# 18_RK3588_PCIE30_PCIE20_SATA30.net
KiCad netlist of a schematic drawn in Altium Designer
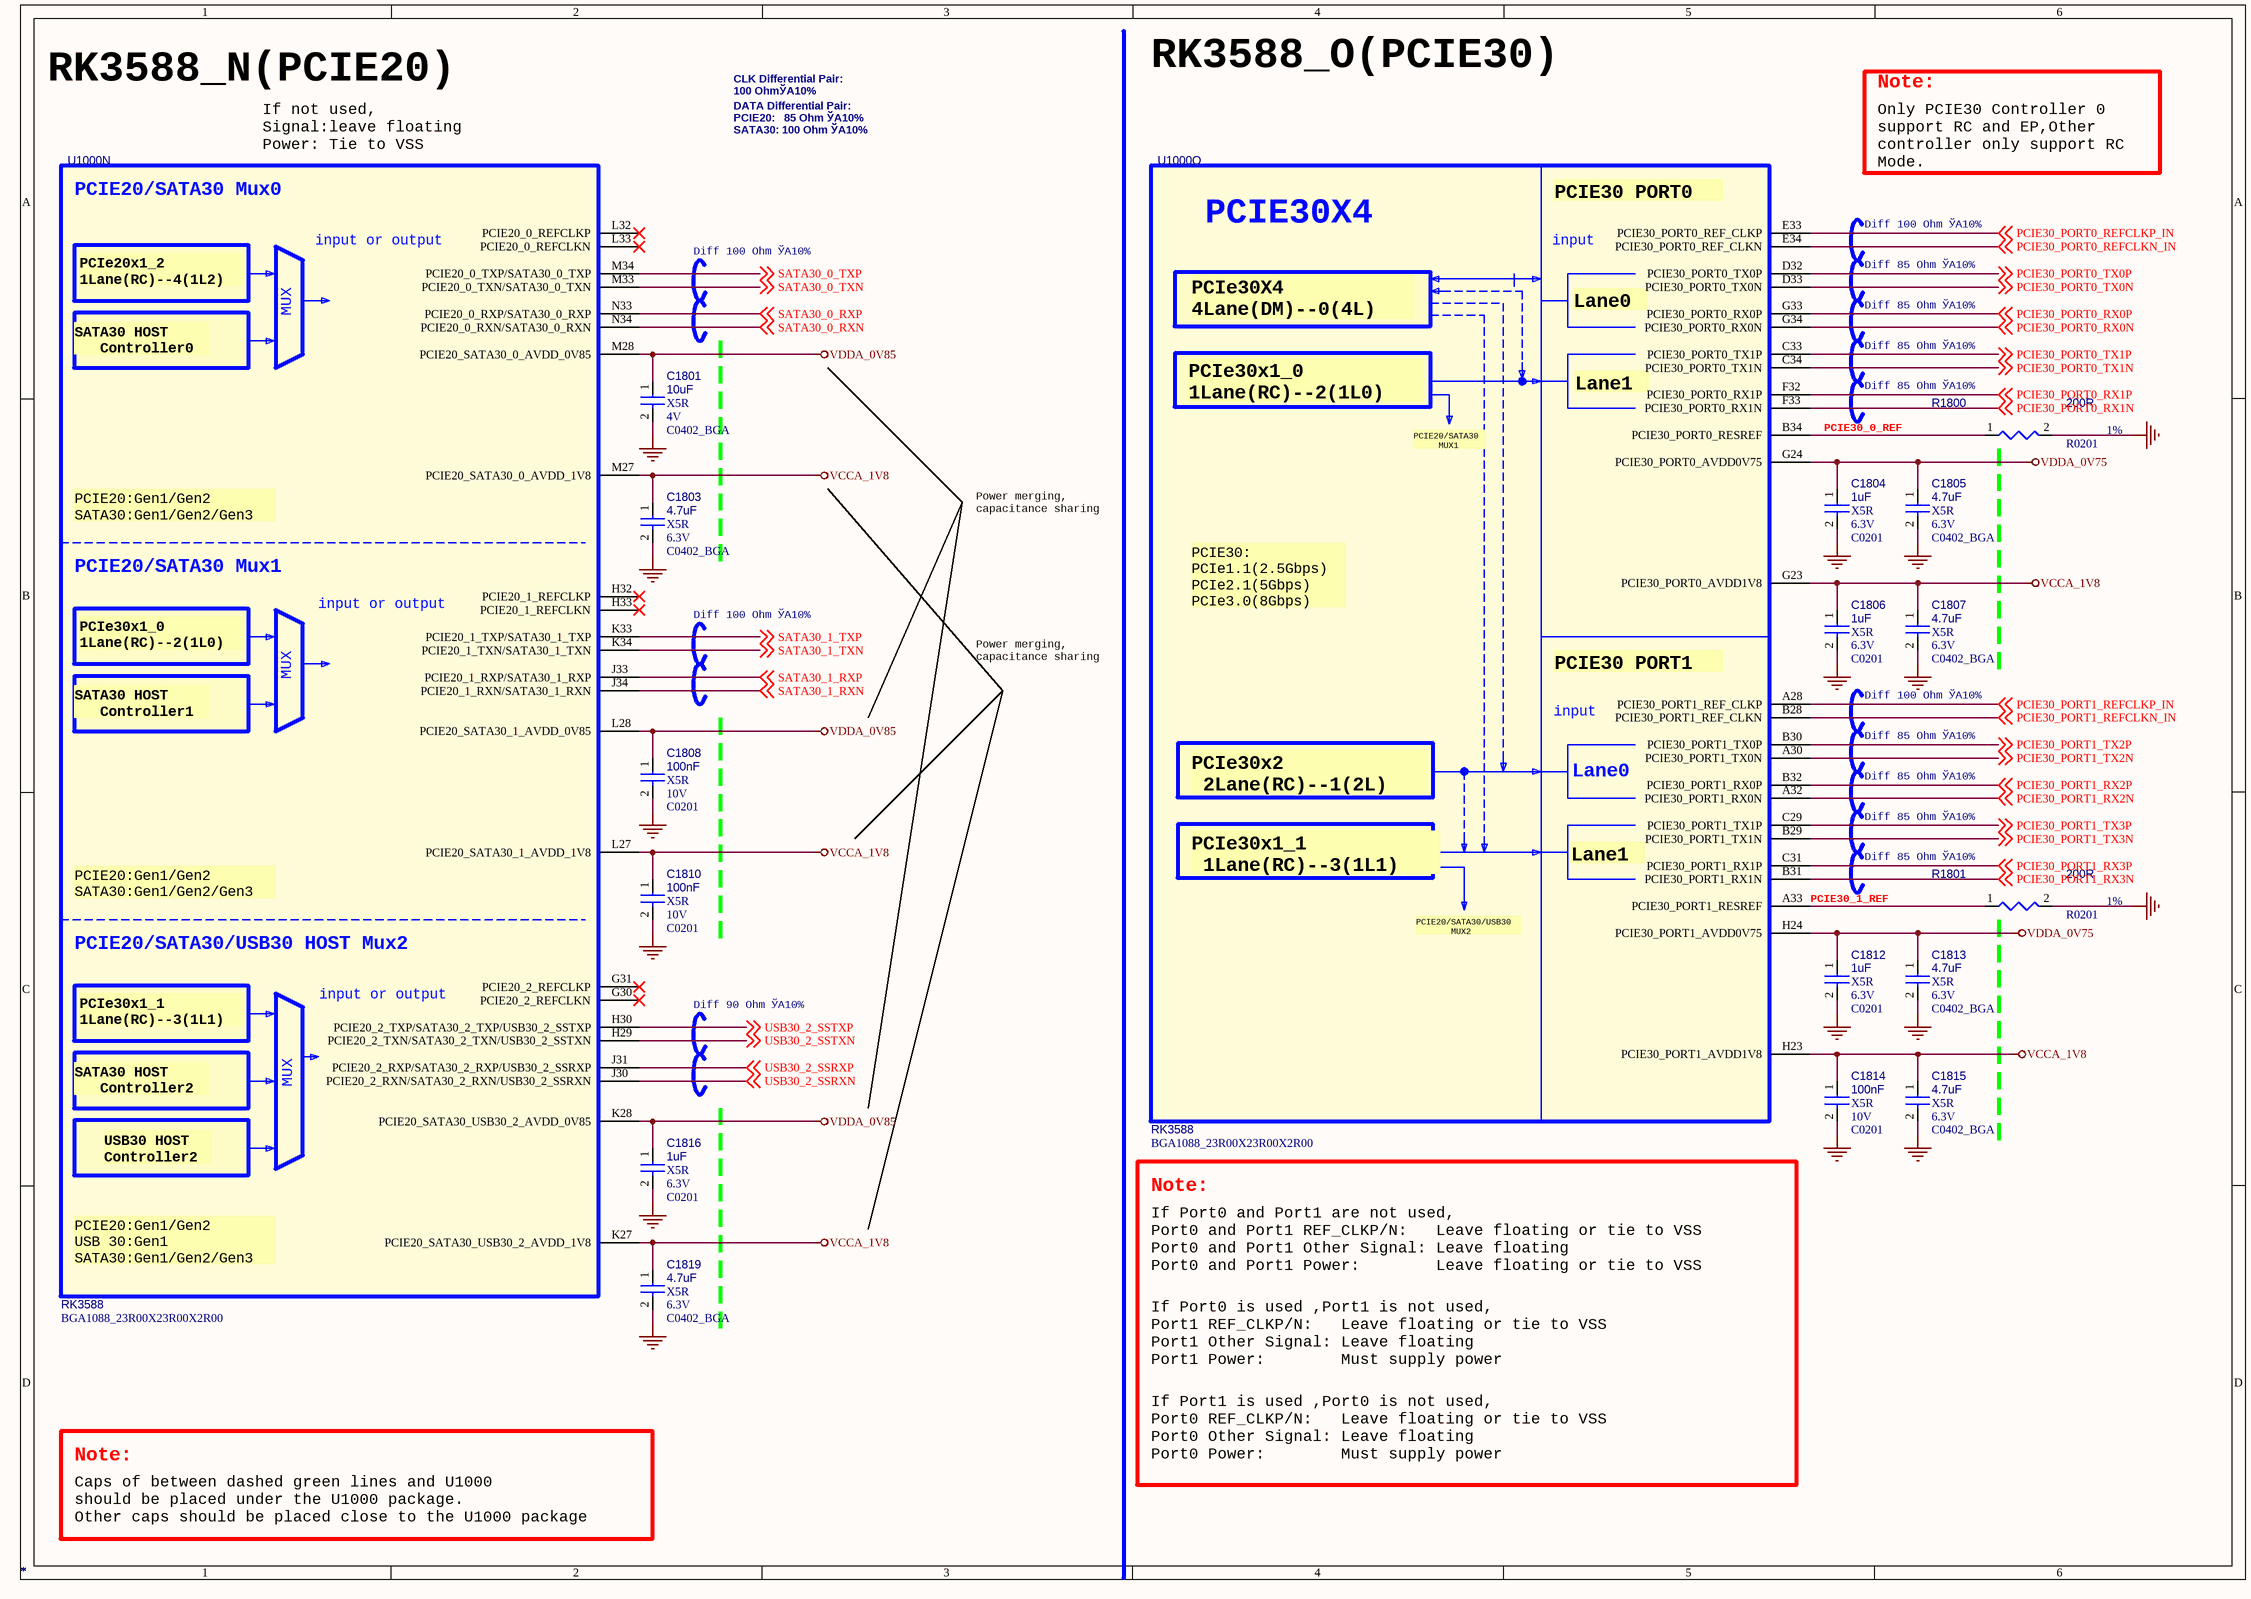
[diagram p0: 18.RK3588_PCIE30_PCIE20_SATA30.SchDoc]

(export (version "E")
  (design (tool "Eeschema 10.0.6"))
  (components
    (comp (ref "C1801")
      (value "*")
      (footprint "C0402_BGA")
      (description "cap,10.00uF,+/-20%,4V,X5R,C0402")
      (fields
        (field (name "VOLTAGE") "4V")
        (field (name "PCB FOOTPRINT") "C0402_BGA")
        (field (name "DIELECTRIC") "X5R")
        (field (name "MANUFACTURER") "YAGEO")
        (field (name "TOLERANCE") "20%")
        (field (name "ALTIUM_UNNAMED_1") "10uF")
        (field (name "CREATED BY") "JJJ")
      )
      (libsource (lib "*") (part "CAP NP"))
    )
    (comp (ref "C1803")
      (value "*")
      (footprint "C0402_BGA")
      (description "cap,4.70uF,+/-10%,6.3V,X5R,C0402")
      (fields
        (field (name "VOLTAGE") "6.3V")
        (field (name "PCB FOOTPRINT") "C0402_BGA")
        (field (name "DIELECTRIC") "X5R")
        (field (name "MANUFACTURER") "TDK")
        (field (name "TOLERANCE") "10%")
        (field (name "ALTIUM_UNNAMED_1") "4.7uF")
        (field (name "CREATED BY") "JJJ")
      )
      (libsource (lib "*") (part "CAP NP"))
    )
    (comp (ref "C1804")
      (value "*")
      (footprint "C0201")
      (description "cap,1.00uF,+/-20%,6.3V,X5R,C0201")
      (fields
        (field (name "VOLTAGE") "6.3V")
        (field (name "PCB FOOTPRINT") "C0201")
        (field (name "DIELECTRIC") "X5R")
        (field (name "TOLERANCE") "20%")
        (field (name "MANUFACTURER") "TDK")
        (field (name "ALTIUM_UNNAMED_1") "1uF")
        (field (name "CREATED BY") "JJJ")
      )
      (libsource (lib "*") (part "CAP NP"))
    )
    (comp (ref "C1805")
      (value "*")
      (footprint "C0402_BGA")
      (description "cap,4.70uF,+/-10%,6.3V,X5R,C0402")
      (fields
        (field (name "VOLTAGE") "6.3V")
        (field (name "PCB FOOTPRINT") "C0402_BGA")
        (field (name "DIELECTRIC") "X5R")
        (field (name "MANUFACTURER") "TDK")
        (field (name "TOLERANCE") "10%")
        (field (name "ALTIUM_UNNAMED_1") "4.7uF")
        (field (name "CREATED BY") "JJJ")
      )
      (libsource (lib "*") (part "CAP NP"))
    )
    (comp (ref "C1806")
      (value "*")
      (footprint "C0201")
      (description "cap,1.00uF,+/-20%,6.3V,X5R,C0201")
      (fields
        (field (name "VOLTAGE") "6.3V")
        (field (name "PCB FOOTPRINT") "C0201")
        (field (name "DIELECTRIC") "X5R")
        (field (name "MANUFACTURER") "TDK")
        (field (name "TOLERANCE") "20%")
        (field (name "ALTIUM_UNNAMED_1") "1uF")
        (field (name "CREATED BY") "JJJ")
      )
      (libsource (lib "*") (part "CAP NP"))
    )
    (comp (ref "C1807")
      (value "*")
      (footprint "C0402_BGA")
      (description "cap,4.70uF,+/-10%,6.3V,X5R,C0402")
      (fields
        (field (name "VOLTAGE") "6.3V")
        (field (name "PCB FOOTPRINT") "C0402_BGA")
        (field (name "DIELECTRIC") "X5R")
        (field (name "MANUFACTURER") "TDK")
        (field (name "TOLERANCE") "10%")
        (field (name "ALTIUM_UNNAMED_1") "4.7uF")
        (field (name "CREATED BY") "JJJ")
      )
      (libsource (lib "*") (part "CAP NP"))
    )
    (comp (ref "C1808")
      (value "*")
      (footprint "C0201")
      (description "cap,100.00nF,+/-10%,10V,X5R,C0201")
      (fields
        (field (name "VOLTAGE") "10V")
        (field (name "PCB FOOTPRINT") "C0201")
        (field (name "DIELECTRIC") "X5R")
        (field (name "MANUFACTURER") "TDK")
        (field (name "TOLERANCE") "10%")
        (field (name "ALTIUM_UNNAMED_1") "100nF")
        (field (name "CREATED BY") "JJJ")
      )
      (libsource (lib "*") (part "CAP NP"))
    )
    (comp (ref "C1810")
      (value "*")
      (footprint "C0201")
      (description "cap,100.00nF,+/-10%,10V,X5R,C0201")
      (fields
        (field (name "VOLTAGE") "10V")
        (field (name "PCB FOOTPRINT") "C0201")
        (field (name "DIELECTRIC") "X5R")
        (field (name "TOLERANCE") "10%")
        (field (name "MANUFACTURER") "TDK")
        (field (name "ALTIUM_UNNAMED_1") "100nF")
        (field (name "CREATED BY") "JJJ")
      )
      (libsource (lib "*") (part "CAP NP"))
    )
    (comp (ref "C1812")
      (value "*")
      (footprint "C0201")
      (description "cap,1.00uF,+/-20%,6.3V,X5R,C0201")
      (fields
        (field (name "VOLTAGE") "6.3V")
        (field (name "PCB FOOTPRINT") "C0201")
        (field (name "DIELECTRIC") "X5R")
        (field (name "TOLERANCE") "20%")
        (field (name "MANUFACTURER") "TDK")
        (field (name "ALTIUM_UNNAMED_1") "1uF")
        (field (name "CREATED BY") "JJJ")
      )
      (libsource (lib "*") (part "CAP NP"))
    )
    (comp (ref "C1813")
      (value "*")
      (footprint "C0402_BGA")
      (description "cap,4.70uF,+/-10%,6.3V,X5R,C0402")
      (fields
        (field (name "VOLTAGE") "6.3V")
        (field (name "PCB FOOTPRINT") "C0402_BGA")
        (field (name "DIELECTRIC") "X5R")
        (field (name "MANUFACTURER") "TDK")
        (field (name "TOLERANCE") "10%")
        (field (name "ALTIUM_UNNAMED_1") "4.7uF")
        (field (name "CREATED BY") "JJJ")
      )
      (libsource (lib "*") (part "CAP NP"))
    )
    (comp (ref "C1814")
      (value "*")
      (footprint "C0201")
      (description "cap,100.00nF,+/-10%,10V,X5R,C0201")
      (fields
        (field (name "VOLTAGE") "10V")
        (field (name "PCB FOOTPRINT") "C0201")
        (field (name "DIELECTRIC") "X5R")
        (field (name "MANUFACTURER") "TDK")
        (field (name "TOLERANCE") "10%")
        (field (name "ALTIUM_UNNAMED_1") "100nF")
        (field (name "CREATED BY") "JJJ")
      )
      (libsource (lib "*") (part "CAP NP"))
    )
    (comp (ref "C1815")
      (value "*")
      (footprint "C0402_BGA")
      (description "cap,4.70uF,+/-10%,6.3V,X5R,C0402")
      (fields
        (field (name "VOLTAGE") "6.3V")
        (field (name "PCB FOOTPRINT") "C0402_BGA")
        (field (name "DIELECTRIC") "X5R")
        (field (name "MANUFACTURER") "TDK")
        (field (name "TOLERANCE") "10%")
        (field (name "ALTIUM_UNNAMED_1") "4.7uF")
        (field (name "CREATED BY") "JJJ")
      )
      (libsource (lib "*") (part "CAP NP"))
    )
    (comp (ref "C1816")
      (value "*")
      (footprint "C0201")
      (description "cap,1.00uF,+/-20%,6.3V,X5R,C0201")
      (fields
        (field (name "VOLTAGE") "6.3V")
        (field (name "PCB FOOTPRINT") "C0201")
        (field (name "DIELECTRIC") "X5R")
        (field (name "MANUFACTURER") "TDK")
        (field (name "TOLERANCE") "20%")
        (field (name "ALTIUM_UNNAMED_1") "1uF")
        (field (name "CREATED BY") "JJJ")
      )
      (libsource (lib "*") (part "CAP NP"))
    )
    (comp (ref "C1819")
      (value "*")
      (footprint "C0402_BGA")
      (description "cap,4.70uF,+/-10%,6.3V,X5R,C0402")
      (fields
        (field (name "VOLTAGE") "6.3V")
        (field (name "PCB FOOTPRINT") "C0402_BGA")
        (field (name "DIELECTRIC") "X5R")
        (field (name "MANUFACTURER") "TDK")
        (field (name "TOLERANCE") "10%")
        (field (name "ALTIUM_UNNAMED_1") "4.7uF")
        (field (name "CREATED BY") "JJJ")
      )
      (libsource (lib "*") (part "CAP NP"))
    )
    (comp (ref "R1800")
      (value "*")
      (footprint "R0402")
      (description "НЁУГєсД¤µзЧи,200R,+/-1%,R0201,1/20W.")
      (fields
        (field (name "PCB FOOTPRINT") "R0201")
        (field (name "TOLERANCE") "1%")
        (field (name "MANUFACTURER") "YAGEO")
        (field (name "ALTIUM_UNNAMED_1") "200R")
        (field (name "CREATED BY") "YTL")
      )
      (libsource (lib "*") (part "RESISTOR_Dup1"))
    )
    (comp (ref "R1801")
      (value "*")
      (footprint "R0402")
      (description "НЁУГєсД¤µзЧи,200R,+/-1%,R0201,1/20W.")
      (fields
        (field (name "PCB FOOTPRINT") "R0201")
        (field (name "TOLERANCE") "1%")
        (field (name "MANUFACTURER") "YAGEO")
        (field (name "ALTIUM_UNNAMED_1") "200R")
        (field (name "CREATED BY") "YTL")
      )
      (libsource (lib "*") (part "RESISTOR_Dup1"))
    )
    (comp (ref "U1000")
      (value "*")
      (footprint "BGA1088_23R00X23R00X2R00")
      (description "ROCKCHIP SOC")
      (fields
        (field (name "MANUFACTURER") "Rockchip (ИрРѕОў)")
        (field (name "PCB FOOTPRINT") "BGA1088_23R00X23R00X2R00")
        (field (name "ALTIUM_UNNAMED_1") "RK3588")
        (field (name "CREATED BY") "YWQ")
      )
      (libsource (lib "*") (part "SOC_RK3588"))
    )
  )
  (nets
    (net (code "1") (name "/PCIE30_0_REF") (class "Default")
      (node (ref "R1800") (pin "1") (pinfunction "1_1") (pintype "passive"))
      (node (ref "U1000") (pin "B34") (pinfunction "PCIE30_PORT0_RESREF_B34") (pintype "passive"))
    )
    (net (code "2") (name "/PCIE30_1_REF") (class "Default")
      (node (ref "R1801") (pin "1") (pinfunction "1_1") (pintype "passive"))
      (node (ref "U1000") (pin "A33") (pinfunction "PCIE30_PORT1_RESREF_A33") (pintype "passive"))
    )
    (net (code "3") (name "GND") (class "Default")
      (node (ref "C1801") (pin "2") (pinfunction "2_2") (pintype "passive"))
      (node (ref "C1803") (pin "2") (pinfunction "2_2") (pintype "passive"))
      (node (ref "C1804") (pin "2") (pinfunction "2_2") (pintype "passive"))
      (node (ref "C1805") (pin "2") (pinfunction "2_2") (pintype "passive"))
      (node (ref "C1806") (pin "2") (pinfunction "2_2") (pintype "passive"))
      (node (ref "C1807") (pin "2") (pinfunction "2_2") (pintype "passive"))
      (node (ref "C1808") (pin "2") (pinfunction "2_2") (pintype "passive"))
      (node (ref "C1810") (pin "2") (pinfunction "2_2") (pintype "passive"))
      (node (ref "C1812") (pin "2") (pinfunction "2_2") (pintype "passive"))
      (node (ref "C1813") (pin "2") (pinfunction "2_2") (pintype "passive"))
      (node (ref "C1814") (pin "2") (pinfunction "2_2") (pintype "passive"))
      (node (ref "C1815") (pin "2") (pinfunction "2_2") (pintype "passive"))
      (node (ref "C1816") (pin "2") (pinfunction "2_2") (pintype "passive"))
      (node (ref "C1819") (pin "2") (pinfunction "2_2") (pintype "passive"))
      (node (ref "R1800") (pin "2") (pinfunction "2_2") (pintype "passive"))
      (node (ref "R1801") (pin "2") (pinfunction "2_2") (pintype "passive"))
    )
    (net (code "4") (name "PCIE30_PORT0_REFCLKN_IN") (class "Default")
      (node (ref "U1000") (pin "E34") (pinfunction "PCIE30_PORT0_REF_CLKN_E34") (pintype "passive"))
    )
    (net (code "5") (name "PCIE30_PORT0_REFCLKP_IN") (class "Default")
      (node (ref "U1000") (pin "E33") (pinfunction "PCIE30_PORT0_REF_CLKP_E33") (pintype "passive"))
    )
    (net (code "6") (name "PCIE30_PORT0_RX0N") (class "Default")
      (node (ref "U1000") (pin "G34") (pinfunction "PCIE30_PORT0_RX0N_G34") (pintype "passive"))
    )
    (net (code "7") (name "PCIE30_PORT0_RX0P") (class "Default")
      (node (ref "U1000") (pin "G33") (pinfunction "PCIE30_PORT0_RX0P_G33") (pintype "passive"))
    )
    (net (code "8") (name "PCIE30_PORT0_RX1N") (class "Default")
      (node (ref "U1000") (pin "F33") (pinfunction "PCIE30_PORT0_RX1N_F33") (pintype "passive"))
    )
    (net (code "9") (name "PCIE30_PORT0_RX1P") (class "Default")
      (node (ref "U1000") (pin "F32") (pinfunction "PCIE30_PORT0_RX1P_F32") (pintype "passive"))
    )
    (net (code "10") (name "PCIE30_PORT0_TX0N") (class "Default")
      (node (ref "U1000") (pin "D33") (pinfunction "PCIE30_PORT0_TX0N_D33") (pintype "passive"))
    )
    (net (code "11") (name "PCIE30_PORT0_TX0P") (class "Default")
      (node (ref "U1000") (pin "D32") (pinfunction "PCIE30_PORT0_TX0P_D32") (pintype "passive"))
    )
    (net (code "12") (name "PCIE30_PORT0_TX1N") (class "Default")
      (node (ref "U1000") (pin "C34") (pinfunction "PCIE30_PORT0_TX1N_C34") (pintype "passive"))
    )
    (net (code "13") (name "PCIE30_PORT0_TX1P") (class "Default")
      (node (ref "U1000") (pin "C33") (pinfunction "PCIE30_PORT0_TX1P_C33") (pintype "passive"))
    )
    (net (code "14") (name "PCIE30_PORT1_REFCLKN_IN") (class "Default")
      (node (ref "U1000") (pin "B28") (pinfunction "PCIE30_PORT1_REF_CLKN_B28") (pintype "passive"))
    )
    (net (code "15") (name "PCIE30_PORT1_REFCLKP_IN") (class "Default")
      (node (ref "U1000") (pin "A28") (pinfunction "PCIE30_PORT1_REF_CLKP_A28") (pintype "passive"))
    )
    (net (code "16") (name "PCIE30_PORT1_RX2N") (class "Default")
      (node (ref "U1000") (pin "A32") (pinfunction "PCIE30_PORT1_RX0N_A32") (pintype "passive"))
    )
    (net (code "17") (name "PCIE30_PORT1_RX2P") (class "Default")
      (node (ref "U1000") (pin "B32") (pinfunction "PCIE30_PORT1_RX0P_B32") (pintype "passive"))
    )
    (net (code "18") (name "PCIE30_PORT1_RX3N") (class "Default")
      (node (ref "U1000") (pin "B31") (pinfunction "PCIE30_PORT1_RX1N_B31") (pintype "passive"))
    )
    (net (code "19") (name "PCIE30_PORT1_RX3P") (class "Default")
      (node (ref "U1000") (pin "C31") (pinfunction "PCIE30_PORT1_RX1P_C31") (pintype "passive"))
    )
    (net (code "20") (name "PCIE30_PORT1_TX2N") (class "Default")
      (node (ref "U1000") (pin "A30") (pinfunction "PCIE30_PORT1_TX0N_A30") (pintype "passive"))
    )
    (net (code "21") (name "PCIE30_PORT1_TX2P") (class "Default")
      (node (ref "U1000") (pin "B30") (pinfunction "PCIE30_PORT1_TX0P_B30") (pintype "passive"))
    )
    (net (code "22") (name "PCIE30_PORT1_TX3N") (class "Default")
      (node (ref "U1000") (pin "B29") (pinfunction "PCIE30_PORT1_TX1N_B29") (pintype "passive"))
    )
    (net (code "23") (name "PCIE30_PORT1_TX3P") (class "Default")
      (node (ref "U1000") (pin "C29") (pinfunction "PCIE30_PORT1_TX1P_C29") (pintype "passive"))
    )
    (net (code "24") (name "SATA30_0_RXN") (class "Default")
      (node (ref "U1000") (pin "N34") (pinfunction "PCIE20_0_RXN/SATA30_0_RXN_N34") (pintype "passive"))
    )
    (net (code "25") (name "SATA30_0_RXP") (class "Default")
      (node (ref "U1000") (pin "N33") (pinfunction "PCIE20_0_RXP/SATA30_0_RXP_N33") (pintype "passive"))
    )
    (net (code "26") (name "SATA30_0_TXN") (class "Default")
      (node (ref "U1000") (pin "M33") (pinfunction "PCIE20_0_TXN/SATA30_0_TXN_M33") (pintype "passive"))
    )
    (net (code "27") (name "SATA30_0_TXP") (class "Default")
      (node (ref "U1000") (pin "M34") (pinfunction "PCIE20_0_TXP/SATA30_0_TXP_M34") (pintype "passive"))
    )
    (net (code "28") (name "SATA30_1_RXN") (class "Default")
      (node (ref "U1000") (pin "J34") (pinfunction "PCIE20_1_RXN/SATA30_1_RXN_J34") (pintype "passive"))
    )
    (net (code "29") (name "SATA30_1_RXP") (class "Default")
      (node (ref "U1000") (pin "J33") (pinfunction "PCIE20_1_RXP/SATA30_1_RXP_J33") (pintype "passive"))
    )
    (net (code "30") (name "SATA30_1_TXN") (class "Default")
      (node (ref "U1000") (pin "K34") (pinfunction "PCIE20_1_TXN/SATA30_1_TXN_K34") (pintype "passive"))
    )
    (net (code "31") (name "SATA30_1_TXP") (class "Default")
      (node (ref "U1000") (pin "K33") (pinfunction "PCIE20_1_TXP/SATA30_1_TXP_K33") (pintype "passive"))
    )
    (net (code "32") (name "USB30_2_SSRXN") (class "Default")
      (node (ref "U1000") (pin "J30") (pinfunction "PCIE20_2_RXN/SATA30_2_RXN/USB30_2_SSRXN_J30") (pintype "passive"))
    )
    (net (code "33") (name "USB30_2_SSRXP") (class "Default")
      (node (ref "U1000") (pin "J31") (pinfunction "PCIE20_2_RXP/SATA30_2_RXP/USB30_2_SSRXP_J31") (pintype "passive"))
    )
    (net (code "34") (name "USB30_2_SSTXN") (class "Default")
      (node (ref "U1000") (pin "H29") (pinfunction "PCIE20_2_TXN/SATA30_2_TXN/USB30_2_SSTXN_H29") (pintype "passive"))
    )
    (net (code "35") (name "USB30_2_SSTXP") (class "Default")
      (node (ref "U1000") (pin "H30") (pinfunction "PCIE20_2_TXP/SATA30_2_TXP/USB30_2_SSTXP_H30") (pintype "passive"))
    )
    (net (code "36") (name "VCCA_1V8") (class "Default")
      (node (ref "C1803") (pin "1") (pinfunction "1_1") (pintype "passive"))
      (node (ref "C1806") (pin "1") (pinfunction "1_1") (pintype "passive"))
      (node (ref "C1807") (pin "1") (pinfunction "1_1") (pintype "passive"))
      (node (ref "C1810") (pin "1") (pinfunction "1_1") (pintype "passive"))
      (node (ref "C1814") (pin "1") (pinfunction "1_1") (pintype "passive"))
      (node (ref "C1815") (pin "1") (pinfunction "1_1") (pintype "passive"))
      (node (ref "C1819") (pin "1") (pinfunction "1_1") (pintype "passive"))
      (node (ref "U1000") (pin "G23") (pinfunction "PCIE30_PORT0_AVDD1V8_G23") (pintype "passive"))
      (node (ref "U1000") (pin "H23") (pinfunction "PCIE30_PORT1_AVDD1V8_H23") (pintype "passive"))
      (node (ref "U1000") (pin "K27") (pinfunction "PCIE20_SATA30_USB30_2_AVDD_1V8_K27") (pintype "passive"))
      (node (ref "U1000") (pin "L27") (pinfunction "PCIE20_SATA30_1_AVDD_1V8_L27") (pintype "passive"))
      (node (ref "U1000") (pin "M27") (pinfunction "PCIE20_SATA30_0_AVDD_1V8_M27") (pintype "passive"))
    )
    (net (code "37") (name "VDDA_0V75") (class "Default")
      (node (ref "C1804") (pin "1") (pinfunction "1_1") (pintype "passive"))
      (node (ref "C1805") (pin "1") (pinfunction "1_1") (pintype "passive"))
      (node (ref "C1812") (pin "1") (pinfunction "1_1") (pintype "passive"))
      (node (ref "C1813") (pin "1") (pinfunction "1_1") (pintype "passive"))
      (node (ref "U1000") (pin "G24") (pinfunction "PCIE30_PORT0_AVDD0V75_G24") (pintype "passive"))
      (node (ref "U1000") (pin "H24") (pinfunction "PCIE30_PORT1_AVDD0V75_H24") (pintype "passive"))
    )
    (net (code "38") (name "VDDA_0V85") (class "Default")
      (node (ref "C1801") (pin "1") (pinfunction "1_1") (pintype "passive"))
      (node (ref "C1808") (pin "1") (pinfunction "1_1") (pintype "passive"))
      (node (ref "C1816") (pin "1") (pinfunction "1_1") (pintype "passive"))
      (node (ref "U1000") (pin "K28") (pinfunction "PCIE20_SATA30_USB30_2_AVDD_0V85_K28") (pintype "passive"))
      (node (ref "U1000") (pin "L28") (pinfunction "PCIE20_SATA30_1_AVDD_0V85_L28") (pintype "passive"))
      (node (ref "U1000") (pin "M28") (pinfunction "PCIE20_SATA30_0_AVDD_0V85_M28") (pintype "passive"))
    )
    (net (code "39") (name "unconnected-(U1000N-PCIE20_0_REFCLKN-PadL33)") (class "Default")
      (node (ref "U1000") (pin "L33") (pinfunction "PCIE20_0_REFCLKN_L33") (pintype "passive+no_connect"))
    )
    (net (code "40") (name "unconnected-(U1000N-PCIE20_0_REFCLKP-PadL32)") (class "Default")
      (node (ref "U1000") (pin "L32") (pinfunction "PCIE20_0_REFCLKP_L32") (pintype "passive+no_connect"))
    )
    (net (code "41") (name "unconnected-(U1000N-PCIE20_1_REFCLKN-PadH33)") (class "Default")
      (node (ref "U1000") (pin "H33") (pinfunction "PCIE20_1_REFCLKN_H33") (pintype "passive+no_connect"))
    )
    (net (code "42") (name "unconnected-(U1000N-PCIE20_1_REFCLKP-PadH32)") (class "Default")
      (node (ref "U1000") (pin "H32") (pinfunction "PCIE20_1_REFCLKP_H32") (pintype "passive+no_connect"))
    )
    (net (code "43") (name "unconnected-(U1000N-PCIE20_2_REFCLKN-PadG30)") (class "Default")
      (node (ref "U1000") (pin "G30") (pinfunction "PCIE20_2_REFCLKN_G30") (pintype "passive+no_connect"))
    )
    (net (code "44") (name "unconnected-(U1000N-PCIE20_2_REFCLKP-PadG31)") (class "Default")
      (node (ref "U1000") (pin "G31") (pinfunction "PCIE20_2_REFCLKP_G31") (pintype "passive+no_connect"))
    )
  )
)
